# Mainboard_MCU_Breakout.net
KiCad netlist of a schematic drawn in Altium Designer
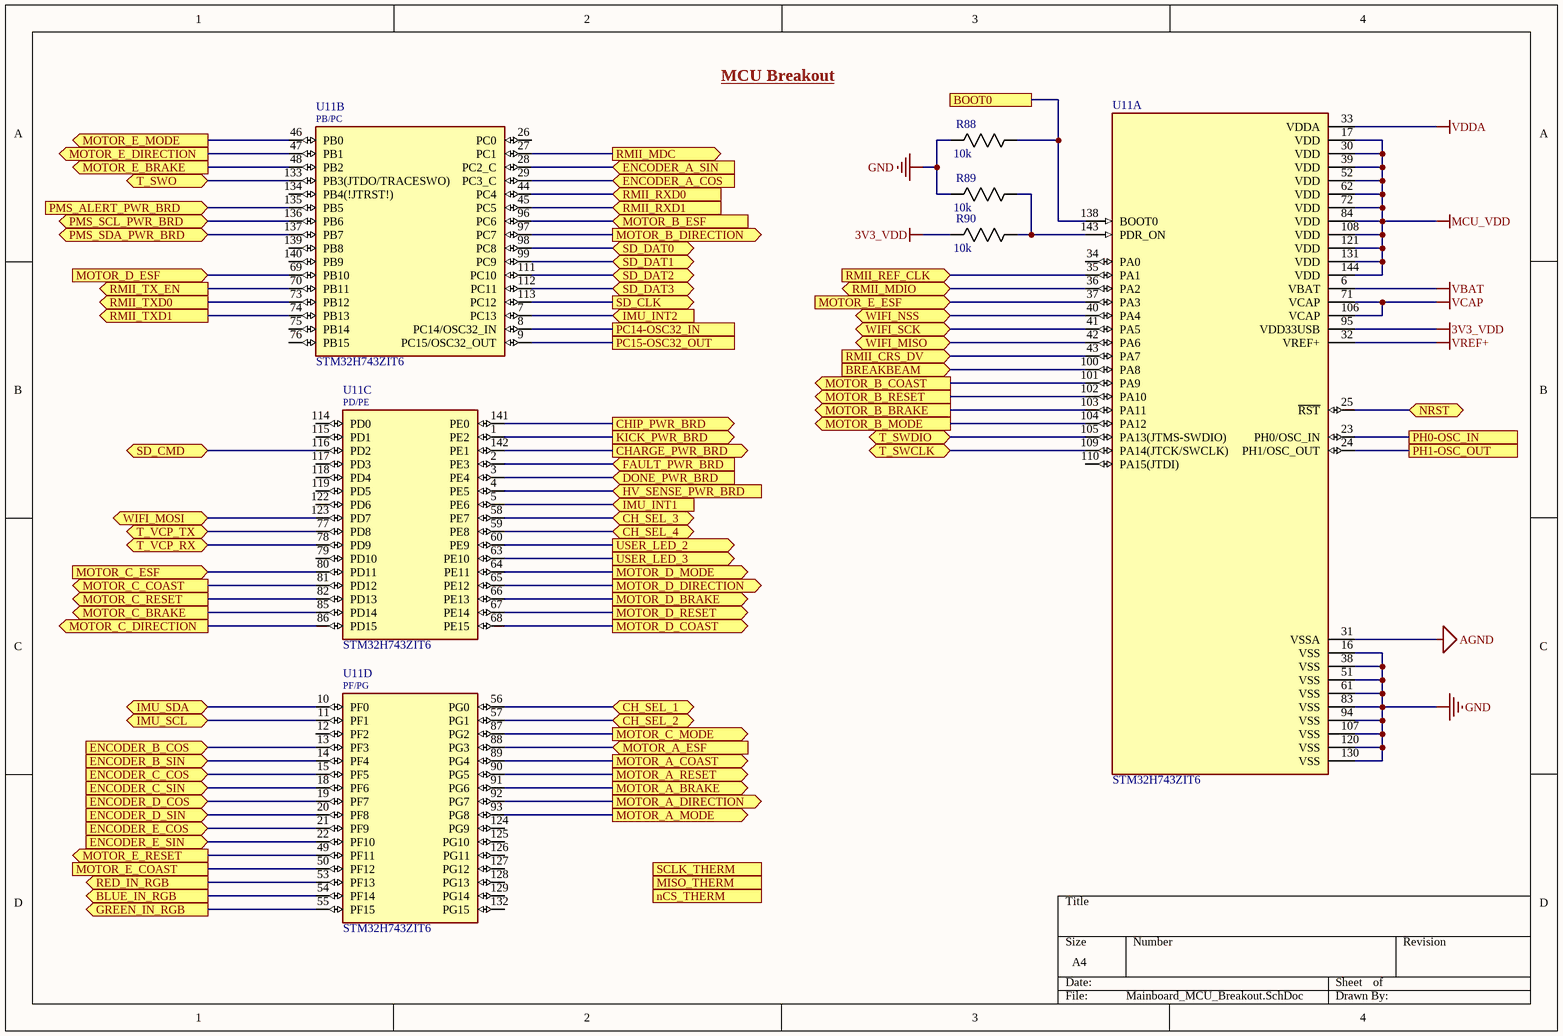
[diagram p0: Mainboard_MCU_Breakout.SchDoc]

(export (version "E")
  (design (tool "Eeschema 10.0.6"))
  (components
    (comp (ref "R88")
      (value "10k")
      (footprint "0805")
      (description "RES SMD 10K OHM 1% 1/8W 0805")
      (fields (field (name "TOLERANCE") "1%"))
      (libsource (lib "") (part "RES 10k 1/8W - 1%_1"))
    )
    (comp (ref "R89")
      (value "10k")
      (footprint "0805")
      (description "RES SMD 10K OHM 1% 1/8W 0805")
      (fields (field (name "TOLERANCE") "1%"))
      (libsource (lib "AltiumLibraries") (part "RES 10k 1/8W - 1%"))
    )
    (comp (ref "R90")
      (value "10k")
      (footprint "0805")
      (description "RES SMD 10K OHM 1% 1/8W 0805")
      (fields (field (name "TOLERANCE") "1%"))
      (libsource (lib "AltiumLibraries") (part "RES 10k 1/8W - 1%"))
    )
    (comp (ref "U11")
      (value "STM32H743ZIT6")
      (footprint "QFP50P2200X2200X160-144N")
      (description "ARM® Cortex®-M7 STM32H7 Microcontroller IC 32-Bit 480MHz 2MB (2M x 8) FLASH 144-LQFP (20x20)")
      (fields (field (name "MF") "STMicroelectronics"))
      (libsource (lib "AltiumLibraries") (part "STM32H743ZIT6"))
    )
  )
  (nets
    (net (code "1") (name "/BLUE_IN_RGB") (class "Default")
      (node (ref "U11") (pin "54") (pinfunction "PF14_54") (pintype "bidirectional"))
    )
    (net (code "2") (name "/BOOT0") (class "Default")
      (node (ref "R88") (pin "1") (pinfunction "R1_1") (pintype "passive"))
      (node (ref "U11") (pin "138") (pinfunction "BOOT0_138") (pintype "input"))
    )
    (net (code "3") (name "/BREAKBEAM") (class "Default")
      (node (ref "U11") (pin "100") (pinfunction "PA8_100") (pintype "bidirectional"))
    )
    (net (code "4") (name "/CHARGE_PWR_BRD") (class "Default")
      (node (ref "U11") (pin "142") (pinfunction "PE1_142") (pintype "bidirectional"))
    )
    (net (code "5") (name "/CHIP_PWR_BRD") (class "Default")
      (node (ref "U11") (pin "141") (pinfunction "PE0_141") (pintype "bidirectional"))
    )
    (net (code "6") (name "/CH_SEL_1") (class "Default")
      (node (ref "U11") (pin "56") (pinfunction "PG0_56") (pintype "bidirectional"))
    )
    (net (code "7") (name "/CH_SEL_2") (class "Default")
      (node (ref "U11") (pin "57") (pinfunction "PG1_57") (pintype "bidirectional"))
    )
    (net (code "8") (name "/CH_SEL_3") (class "Default")
      (node (ref "U11") (pin "58") (pinfunction "PE7_58") (pintype "bidirectional"))
    )
    (net (code "9") (name "/CH_SEL_4") (class "Default")
      (node (ref "U11") (pin "59") (pinfunction "PE8_59") (pintype "bidirectional"))
    )
    (net (code "10") (name "/DONE_PWR_BRD") (class "Default")
      (node (ref "U11") (pin "3") (pinfunction "PE4_3") (pintype "bidirectional"))
    )
    (net (code "11") (name "/ENCODER_A_COS") (class "Default")
      (node (ref "U11") (pin "29") (pinfunction "PC3_C_29") (pintype "bidirectional"))
    )
    (net (code "12") (name "/ENCODER_A_SIN") (class "Default")
      (node (ref "U11") (pin "28") (pinfunction "PC2_C_28") (pintype "bidirectional"))
    )
    (net (code "13") (name "/ENCODER_B_COS") (class "Default")
      (node (ref "U11") (pin "13") (pinfunction "PF3_13") (pintype "bidirectional"))
    )
    (net (code "14") (name "/ENCODER_B_SIN") (class "Default")
      (node (ref "U11") (pin "14") (pinfunction "PF4_14") (pintype "bidirectional"))
    )
    (net (code "15") (name "/ENCODER_C_COS") (class "Default")
      (node (ref "U11") (pin "15") (pinfunction "PF5_15") (pintype "bidirectional"))
    )
    (net (code "16") (name "/ENCODER_C_SIN") (class "Default")
      (node (ref "U11") (pin "18") (pinfunction "PF6_18") (pintype "bidirectional"))
    )
    (net (code "17") (name "/ENCODER_D_COS") (class "Default")
      (node (ref "U11") (pin "19") (pinfunction "PF7_19") (pintype "bidirectional"))
    )
    (net (code "18") (name "/ENCODER_D_SIN") (class "Default")
      (node (ref "U11") (pin "20") (pinfunction "PF8_20") (pintype "bidirectional"))
    )
    (net (code "19") (name "/ENCODER_E_COS") (class "Default")
      (node (ref "U11") (pin "21") (pinfunction "PF9_21") (pintype "bidirectional"))
    )
    (net (code "20") (name "/ENCODER_E_SIN") (class "Default")
      (node (ref "U11") (pin "22") (pinfunction "PF10_22") (pintype "bidirectional"))
    )
    (net (code "21") (name "/FAULT_PWR_BRD") (class "Default")
      (node (ref "U11") (pin "2") (pinfunction "PE3_2") (pintype "bidirectional"))
    )
    (net (code "22") (name "/GREEN_IN_RGB") (class "Default")
      (node (ref "U11") (pin "55") (pinfunction "PF15_55") (pintype "bidirectional"))
    )
    (net (code "23") (name "/HV_SENSE_PWR_BRD") (class "Default")
      (node (ref "U11") (pin "4") (pinfunction "PE5_4") (pintype "bidirectional"))
    )
    (net (code "24") (name "/IMU_INT1") (class "Default")
      (node (ref "U11") (pin "5") (pinfunction "PE6_5") (pintype "bidirectional"))
    )
    (net (code "25") (name "/IMU_INT2") (class "Default")
      (node (ref "U11") (pin "7") (pinfunction "PC13_7") (pintype "bidirectional"))
    )
    (net (code "26") (name "/IMU_SCL") (class "Default")
      (node (ref "U11") (pin "11") (pinfunction "PF1_11") (pintype "bidirectional"))
    )
    (net (code "27") (name "/IMU_SDA") (class "Default")
      (node (ref "U11") (pin "10") (pinfunction "PF0_10") (pintype "bidirectional"))
    )
    (net (code "28") (name "/KICK_PWR_BRD") (class "Default")
      (node (ref "U11") (pin "1") (pinfunction "PE2_1") (pintype "bidirectional"))
    )
    (net (code "30") (name "/MOTOR_A_BRAKE") (class "Default")
      (node (ref "U11") (pin "91") (pinfunction "PG6_91") (pintype "bidirectional"))
    )
    (net (code "31") (name "/MOTOR_A_COAST") (class "Default")
      (node (ref "U11") (pin "89") (pinfunction "PG4_89") (pintype "bidirectional"))
    )
    (net (code "32") (name "/MOTOR_A_DIRECTION") (class "Default")
      (node (ref "U11") (pin "92") (pinfunction "PG7_92") (pintype "bidirectional"))
    )
    (net (code "33") (name "/MOTOR_A_ESF") (class "Default")
      (node (ref "U11") (pin "88") (pinfunction "PG3_88") (pintype "bidirectional"))
    )
    (net (code "34") (name "/MOTOR_A_MODE") (class "Default")
      (node (ref "U11") (pin "93") (pinfunction "PG8_93") (pintype "bidirectional"))
    )
    (net (code "35") (name "/MOTOR_A_RESET") (class "Default")
      (node (ref "U11") (pin "90") (pinfunction "PG5_90") (pintype "bidirectional"))
    )
    (net (code "36") (name "/MOTOR_B_BRAKE") (class "Default")
      (node (ref "U11") (pin "103") (pinfunction "PA11_103") (pintype "bidirectional"))
    )
    (net (code "37") (name "/MOTOR_B_COAST") (class "Default")
      (node (ref "U11") (pin "101") (pinfunction "PA9_101") (pintype "bidirectional"))
    )
    (net (code "38") (name "/MOTOR_B_DIRECTION") (class "Default")
      (node (ref "U11") (pin "97") (pinfunction "PC7_97") (pintype "bidirectional"))
    )
    (net (code "39") (name "/MOTOR_B_ESF") (class "Default")
      (node (ref "U11") (pin "96") (pinfunction "PC6_96") (pintype "bidirectional"))
    )
    (net (code "40") (name "/MOTOR_B_MODE") (class "Default")
      (node (ref "U11") (pin "104") (pinfunction "PA12_104") (pintype "bidirectional"))
    )
    (net (code "41") (name "/MOTOR_B_RESET") (class "Default")
      (node (ref "U11") (pin "102") (pinfunction "PA10_102") (pintype "bidirectional"))
    )
    (net (code "42") (name "/MOTOR_C_BRAKE") (class "Default")
      (node (ref "U11") (pin "85") (pinfunction "PD14_85") (pintype "bidirectional"))
    )
    (net (code "43") (name "/MOTOR_C_COAST") (class "Default")
      (node (ref "U11") (pin "81") (pinfunction "PD12_81") (pintype "bidirectional"))
    )
    (net (code "44") (name "/MOTOR_C_DIRECTION") (class "Default")
      (node (ref "U11") (pin "86") (pinfunction "PD15_86") (pintype "bidirectional"))
    )
    (net (code "45") (name "/MOTOR_C_ESF") (class "Default")
      (node (ref "U11") (pin "80") (pinfunction "PD11_80") (pintype "bidirectional"))
    )
    (net (code "46") (name "/MOTOR_C_MODE") (class "Default")
      (node (ref "U11") (pin "87") (pinfunction "PG2_87") (pintype "bidirectional"))
    )
    (net (code "47") (name "/MOTOR_C_RESET") (class "Default")
      (node (ref "U11") (pin "82") (pinfunction "PD13_82") (pintype "bidirectional"))
    )
    (net (code "48") (name "/MOTOR_D_BRAKE") (class "Default")
      (node (ref "U11") (pin "66") (pinfunction "PE13_66") (pintype "bidirectional"))
    )
    (net (code "49") (name "/MOTOR_D_COAST") (class "Default")
      (node (ref "U11") (pin "68") (pinfunction "PE15_68") (pintype "bidirectional"))
    )
    (net (code "50") (name "/MOTOR_D_DIRECTION") (class "Default")
      (node (ref "U11") (pin "65") (pinfunction "PE12_65") (pintype "bidirectional"))
    )
    (net (code "51") (name "/MOTOR_D_ESF") (class "Default")
      (node (ref "U11") (pin "69") (pinfunction "PB10_69") (pintype "bidirectional"))
    )
    (net (code "52") (name "/MOTOR_D_MODE") (class "Default")
      (node (ref "U11") (pin "64") (pinfunction "PE11_64") (pintype "bidirectional"))
    )
    (net (code "53") (name "/MOTOR_D_RESET") (class "Default")
      (node (ref "U11") (pin "67") (pinfunction "PE14_67") (pintype "bidirectional"))
    )
    (net (code "54") (name "/MOTOR_E_BRAKE") (class "Default")
      (node (ref "U11") (pin "48") (pinfunction "PB2_48") (pintype "bidirectional"))
    )
    (net (code "55") (name "/MOTOR_E_COAST") (class "Default")
      (node (ref "U11") (pin "50") (pinfunction "PF12_50") (pintype "bidirectional"))
    )
    (net (code "56") (name "/MOTOR_E_DIRECTION") (class "Default")
      (node (ref "U11") (pin "47") (pinfunction "PB1_47") (pintype "bidirectional"))
    )
    (net (code "57") (name "/MOTOR_E_ESF") (class "Default")
      (node (ref "U11") (pin "37") (pinfunction "PA3_37") (pintype "bidirectional"))
    )
    (net (code "58") (name "/MOTOR_E_MODE") (class "Default")
      (node (ref "U11") (pin "46") (pinfunction "PB0_46") (pintype "bidirectional"))
    )
    (net (code "59") (name "/MOTOR_E_RESET") (class "Default")
      (node (ref "U11") (pin "49") (pinfunction "PF11_49") (pintype "bidirectional"))
    )
    (net (code "60") (name "/NRST") (class "Default")
      (node (ref "U11") (pin "25") (pinfunction "~{RST}_25") (pintype "bidirectional"))
    )
    (net (code "61") (name "/PC14-OSC32_IN") (class "Default")
      (node (ref "U11") (pin "8") (pinfunction "PC14/OSC32_IN_8") (pintype "bidirectional"))
    )
    (net (code "62") (name "/PC15-OSC32_OUT") (class "Default")
      (node (ref "U11") (pin "9") (pinfunction "PC15/OSC32_OUT_9") (pintype "bidirectional"))
    )
    (net (code "63") (name "/PH0-OSC_IN") (class "Default")
      (node (ref "U11") (pin "23") (pinfunction "PH0/OSC_IN_23") (pintype "bidirectional"))
    )
    (net (code "64") (name "/PH1-OSC_OUT") (class "Default")
      (node (ref "U11") (pin "24") (pinfunction "PH1/OSC_OUT_24") (pintype "bidirectional"))
    )
    (net (code "65") (name "/PMS_ALERT_PWR_BRD") (class "Default")
      (node (ref "U11") (pin "135") (pinfunction "PB5_135") (pintype "bidirectional"))
    )
    (net (code "66") (name "/PMS_SCL_PWR_BRD") (class "Default")
      (node (ref "U11") (pin "136") (pinfunction "PB6_136") (pintype "bidirectional"))
    )
    (net (code "67") (name "/PMS_SDA_PWR_BRD") (class "Default")
      (node (ref "U11") (pin "137") (pinfunction "PB7_137") (pintype "bidirectional"))
    )
    (net (code "68") (name "/RED_IN_RGB") (class "Default")
      (node (ref "U11") (pin "53") (pinfunction "PF13_53") (pintype "bidirectional"))
    )
    (net (code "69") (name "/RMII_CRS_DV") (class "Default")
      (node (ref "U11") (pin "43") (pinfunction "PA7_43") (pintype "bidirectional"))
    )
    (net (code "70") (name "/RMII_MDC") (class "Default")
      (node (ref "U11") (pin "27") (pinfunction "PC1_27") (pintype "bidirectional"))
    )
    (net (code "71") (name "/RMII_MDIO") (class "Default")
      (node (ref "U11") (pin "36") (pinfunction "PA2_36") (pintype "bidirectional"))
    )
    (net (code "72") (name "/RMII_REF_CLK") (class "Default")
      (node (ref "U11") (pin "35") (pinfunction "PA1_35") (pintype "bidirectional"))
    )
    (net (code "73") (name "/RMII_RXD0") (class "Default")
      (node (ref "U11") (pin "44") (pinfunction "PC4_44") (pintype "bidirectional"))
    )
    (net (code "74") (name "/RMII_RXD1") (class "Default")
      (node (ref "U11") (pin "45") (pinfunction "PC5_45") (pintype "bidirectional"))
    )
    (net (code "75") (name "/RMII_TXD0") (class "Default")
      (node (ref "U11") (pin "73") (pinfunction "PB12_73") (pintype "bidirectional"))
    )
    (net (code "76") (name "/RMII_TXD1") (class "Default")
      (node (ref "U11") (pin "74") (pinfunction "PB13_74") (pintype "bidirectional"))
    )
    (net (code "77") (name "/RMII_TX_EN") (class "Default")
      (node (ref "U11") (pin "70") (pinfunction "PB11_70") (pintype "bidirectional"))
    )
    (net (code "79") (name "/SD_CLK") (class "Default")
      (node (ref "U11") (pin "113") (pinfunction "PC12_113") (pintype "bidirectional"))
    )
    (net (code "80") (name "/SD_CMD") (class "Default")
      (node (ref "U11") (pin "116") (pinfunction "PD2_116") (pintype "bidirectional"))
    )
    (net (code "81") (name "/SD_DAT0") (class "Default")
      (node (ref "U11") (pin "98") (pinfunction "PC8_98") (pintype "bidirectional"))
    )
    (net (code "82") (name "/SD_DAT1") (class "Default")
      (node (ref "U11") (pin "99") (pinfunction "PC9_99") (pintype "bidirectional"))
    )
    (net (code "83") (name "/SD_DAT2") (class "Default")
      (node (ref "U11") (pin "111") (pinfunction "PC10_111") (pintype "bidirectional"))
    )
    (net (code "84") (name "/SD_DAT3") (class "Default")
      (node (ref "U11") (pin "112") (pinfunction "PC11_112") (pintype "bidirectional"))
    )
    (net (code "85") (name "/T_SWCLK") (class "Default")
      (node (ref "U11") (pin "109") (pinfunction "PA14(JTCK/SWCLK)_109") (pintype "bidirectional"))
    )
    (net (code "86") (name "/T_SWDIO") (class "Default")
      (node (ref "U11") (pin "105") (pinfunction "PA13(JTMS-SWDIO)_105") (pintype "bidirectional"))
    )
    (net (code "87") (name "/T_SWO") (class "Default")
      (node (ref "U11") (pin "133") (pinfunction "PB3(JTDO/TRACESWO)_133") (pintype "bidirectional"))
    )
    (net (code "88") (name "/T_VCP_RX") (class "Default")
      (node (ref "U11") (pin "78") (pinfunction "PD9_78") (pintype "bidirectional"))
    )
    (net (code "89") (name "/T_VCP_TX") (class "Default")
      (node (ref "U11") (pin "77") (pinfunction "PD8_77") (pintype "bidirectional"))
    )
    (net (code "90") (name "/USER_LED_2") (class "Default")
      (node (ref "U11") (pin "60") (pinfunction "PE9_60") (pintype "bidirectional"))
    )
    (net (code "91") (name "/USER_LED_3") (class "Default")
      (node (ref "U11") (pin "63") (pinfunction "PE10_63") (pintype "bidirectional"))
    )
    (net (code "92") (name "/WIFI_MISO") (class "Default")
      (node (ref "U11") (pin "42") (pinfunction "PA6_42") (pintype "bidirectional"))
    )
    (net (code "93") (name "/WIFI_MOSI") (class "Default")
      (node (ref "U11") (pin "123") (pinfunction "PD7_123") (pintype "bidirectional"))
    )
    (net (code "94") (name "/WIFI_NSS") (class "Default")
      (node (ref "U11") (pin "40") (pinfunction "PA4_40") (pintype "bidirectional"))
    )
    (net (code "95") (name "/WIFI_SCK") (class "Default")
      (node (ref "U11") (pin "41") (pinfunction "PA5_41") (pintype "bidirectional"))
    )
    (net (code "97") (name "3V3_VDD") (class "Default")
      (node (ref "R90") (pin "2") (pinfunction "R2_2") (pintype "passive"))
      (node (ref "U11") (pin "95") (pinfunction "VDD33USB_95") (pintype "power_in"))
    )
    (net (code "98") (name "AGND") (class "Default")
      (node (ref "U11") (pin "31") (pinfunction "VSSA_31") (pintype "power_in"))
    )
    (net (code "99") (name "GND") (class "Default")
      (node (ref "R88") (pin "2") (pinfunction "R2_2") (pintype "passive"))
      (node (ref "R89") (pin "2") (pinfunction "R2_2") (pintype "passive"))
      (node (ref "U11") (pin "107") (pinfunction "VSS_107") (pintype "power_in"))
      (node (ref "U11") (pin "120") (pinfunction "VSS_120") (pintype "power_in"))
      (node (ref "U11") (pin "130") (pinfunction "VSS_130") (pintype "power_in"))
      (node (ref "U11") (pin "16") (pinfunction "VSS_16") (pintype "power_in"))
      (node (ref "U11") (pin "38") (pinfunction "VSS_38") (pintype "power_in"))
      (node (ref "U11") (pin "51") (pinfunction "VSS_51") (pintype "power_in"))
      (node (ref "U11") (pin "61") (pinfunction "VSS_61") (pintype "power_in"))
      (node (ref "U11") (pin "83") (pinfunction "VSS_83") (pintype "power_in"))
      (node (ref "U11") (pin "94") (pinfunction "VSS_94") (pintype "power_in"))
    )
    (net (code "100") (name "MCU_VDD") (class "Default")
      (node (ref "U11") (pin "108") (pinfunction "VDD_108") (pintype "power_in"))
      (node (ref "U11") (pin "121") (pinfunction "VDD_121") (pintype "power_in"))
      (node (ref "U11") (pin "131") (pinfunction "VDD_131") (pintype "power_in"))
      (node (ref "U11") (pin "144") (pinfunction "VDD_144") (pintype "power_in"))
      (node (ref "U11") (pin "17") (pinfunction "VDD_17") (pintype "power_in"))
      (node (ref "U11") (pin "30") (pinfunction "VDD_30") (pintype "power_in"))
      (node (ref "U11") (pin "39") (pinfunction "VDD_39") (pintype "power_in"))
      (node (ref "U11") (pin "52") (pinfunction "VDD_52") (pintype "power_in"))
      (node (ref "U11") (pin "62") (pinfunction "VDD_62") (pintype "power_in"))
      (node (ref "U11") (pin "72") (pinfunction "VDD_72") (pintype "power_in"))
      (node (ref "U11") (pin "84") (pinfunction "VDD_84") (pintype "power_in"))
    )
    (net (code "101") (name "Net-(R89-R1)") (class "Default")
      (node (ref "R89") (pin "1") (pinfunction "R1_1") (pintype "passive"))
      (node (ref "R90") (pin "1") (pinfunction "R1_1") (pintype "passive"))
      (node (ref "U11") (pin "143") (pinfunction "PDR_ON_143") (pintype "input"))
    )
    (net (code "102") (name "VBAT") (class "Default")
      (node (ref "U11") (pin "6") (pinfunction "VBAT_6") (pintype "power_in"))
    )
    (net (code "103") (name "VCAP") (class "Default")
      (node (ref "U11") (pin "106") (pinfunction "VCAP_106") (pintype "power_in"))
      (node (ref "U11") (pin "71") (pinfunction "VCAP_71") (pintype "power_in"))
    )
    (net (code "104") (name "VDDA") (class "Default")
      (node (ref "U11") (pin "33") (pinfunction "VDDA_33") (pintype "power_in"))
    )
    (net (code "105") (name "VREF+") (class "Default")
      (node (ref "U11") (pin "32") (pinfunction "VREF+_32") (pintype "power_in"))
    )
    (net (code "106") (name "unconnected-(U11A-PA0-Pad34)") (class "Default")
      (node (ref "U11") (pin "34") (pinfunction "PA0_34") (pintype "bidirectional"))
    )
    (net (code "107") (name "unconnected-(U11A-PA15(JTDI)-Pad110)") (class "Default")
      (node (ref "U11") (pin "110") (pinfunction "PA15(JTDI)_110") (pintype "bidirectional"))
    )
    (net (code "108") (name "unconnected-(U11B-PB4(!JTRST!)-Pad134)") (class "Default")
      (node (ref "U11") (pin "134") (pinfunction "PB4(!JTRST!)_134") (pintype "bidirectional"))
    )
    (net (code "109") (name "unconnected-(U11B-PB8-Pad139)") (class "Default")
      (node (ref "U11") (pin "139") (pinfunction "PB8_139") (pintype "bidirectional"))
    )
    (net (code "110") (name "unconnected-(U11B-PB9-Pad140)") (class "Default")
      (node (ref "U11") (pin "140") (pinfunction "PB9_140") (pintype "bidirectional"))
    )
    (net (code "111") (name "unconnected-(U11B-PB14-Pad75)") (class "Default")
      (node (ref "U11") (pin "75") (pinfunction "PB14_75") (pintype "bidirectional"))
    )
    (net (code "112") (name "unconnected-(U11B-PB15-Pad76)") (class "Default")
      (node (ref "U11") (pin "76") (pinfunction "PB15_76") (pintype "bidirectional"))
    )
    (net (code "113") (name "unconnected-(U11B-PC0-Pad26)") (class "Default")
      (node (ref "U11") (pin "26") (pinfunction "PC0_26") (pintype "bidirectional"))
    )
    (net (code "114") (name "unconnected-(U11C-PD0-Pad114)") (class "Default")
      (node (ref "U11") (pin "114") (pinfunction "PD0_114") (pintype "bidirectional"))
    )
    (net (code "115") (name "unconnected-(U11C-PD1-Pad115)") (class "Default")
      (node (ref "U11") (pin "115") (pinfunction "PD1_115") (pintype "bidirectional"))
    )
    (net (code "116") (name "unconnected-(U11C-PD3-Pad117)") (class "Default")
      (node (ref "U11") (pin "117") (pinfunction "PD3_117") (pintype "bidirectional"))
    )
    (net (code "117") (name "unconnected-(U11C-PD4-Pad118)") (class "Default")
      (node (ref "U11") (pin "118") (pinfunction "PD4_118") (pintype "bidirectional"))
    )
    (net (code "118") (name "unconnected-(U11C-PD5-Pad119)") (class "Default")
      (node (ref "U11") (pin "119") (pinfunction "PD5_119") (pintype "bidirectional"))
    )
    (net (code "119") (name "unconnected-(U11C-PD6-Pad122)") (class "Default")
      (node (ref "U11") (pin "122") (pinfunction "PD6_122") (pintype "bidirectional"))
    )
    (net (code "120") (name "unconnected-(U11C-PD10-Pad79)") (class "Default")
      (node (ref "U11") (pin "79") (pinfunction "PD10_79") (pintype "bidirectional"))
    )
    (net (code "121") (name "unconnected-(U11D-PF2-Pad12)") (class "Default")
      (node (ref "U11") (pin "12") (pinfunction "PF2_12") (pintype "bidirectional"))
    )
    (net (code "122") (name "unconnected-(U11D-PG9-Pad124)") (class "Default")
      (node (ref "U11") (pin "124") (pinfunction "PG9_124") (pintype "bidirectional"))
    )
    (net (code "123") (name "unconnected-(U11D-PG10-Pad125)") (class "Default")
      (node (ref "U11") (pin "125") (pinfunction "PG10_125") (pintype "bidirectional"))
    )
    (net (code "124") (name "unconnected-(U11D-PG11-Pad126)") (class "Default")
      (node (ref "U11") (pin "126") (pinfunction "PG11_126") (pintype "bidirectional"))
    )
    (net (code "125") (name "unconnected-(U11D-PG12-Pad127)") (class "Default")
      (node (ref "U11") (pin "127") (pinfunction "PG12_127") (pintype "bidirectional"))
    )
    (net (code "126") (name "unconnected-(U11D-PG13-Pad128)") (class "Default")
      (node (ref "U11") (pin "128") (pinfunction "PG13_128") (pintype "bidirectional"))
    )
    (net (code "127") (name "unconnected-(U11D-PG14-Pad129)") (class "Default")
      (node (ref "U11") (pin "129") (pinfunction "PG14_129") (pintype "bidirectional"))
    )
    (net (code "128") (name "unconnected-(U11D-PG15-Pad132)") (class "Default")
      (node (ref "U11") (pin "132") (pinfunction "PG15_132") (pintype "bidirectional"))
    )
  )
)
